# theswitch.net
KiCad netlist of a schematic drawn in Altium Designer
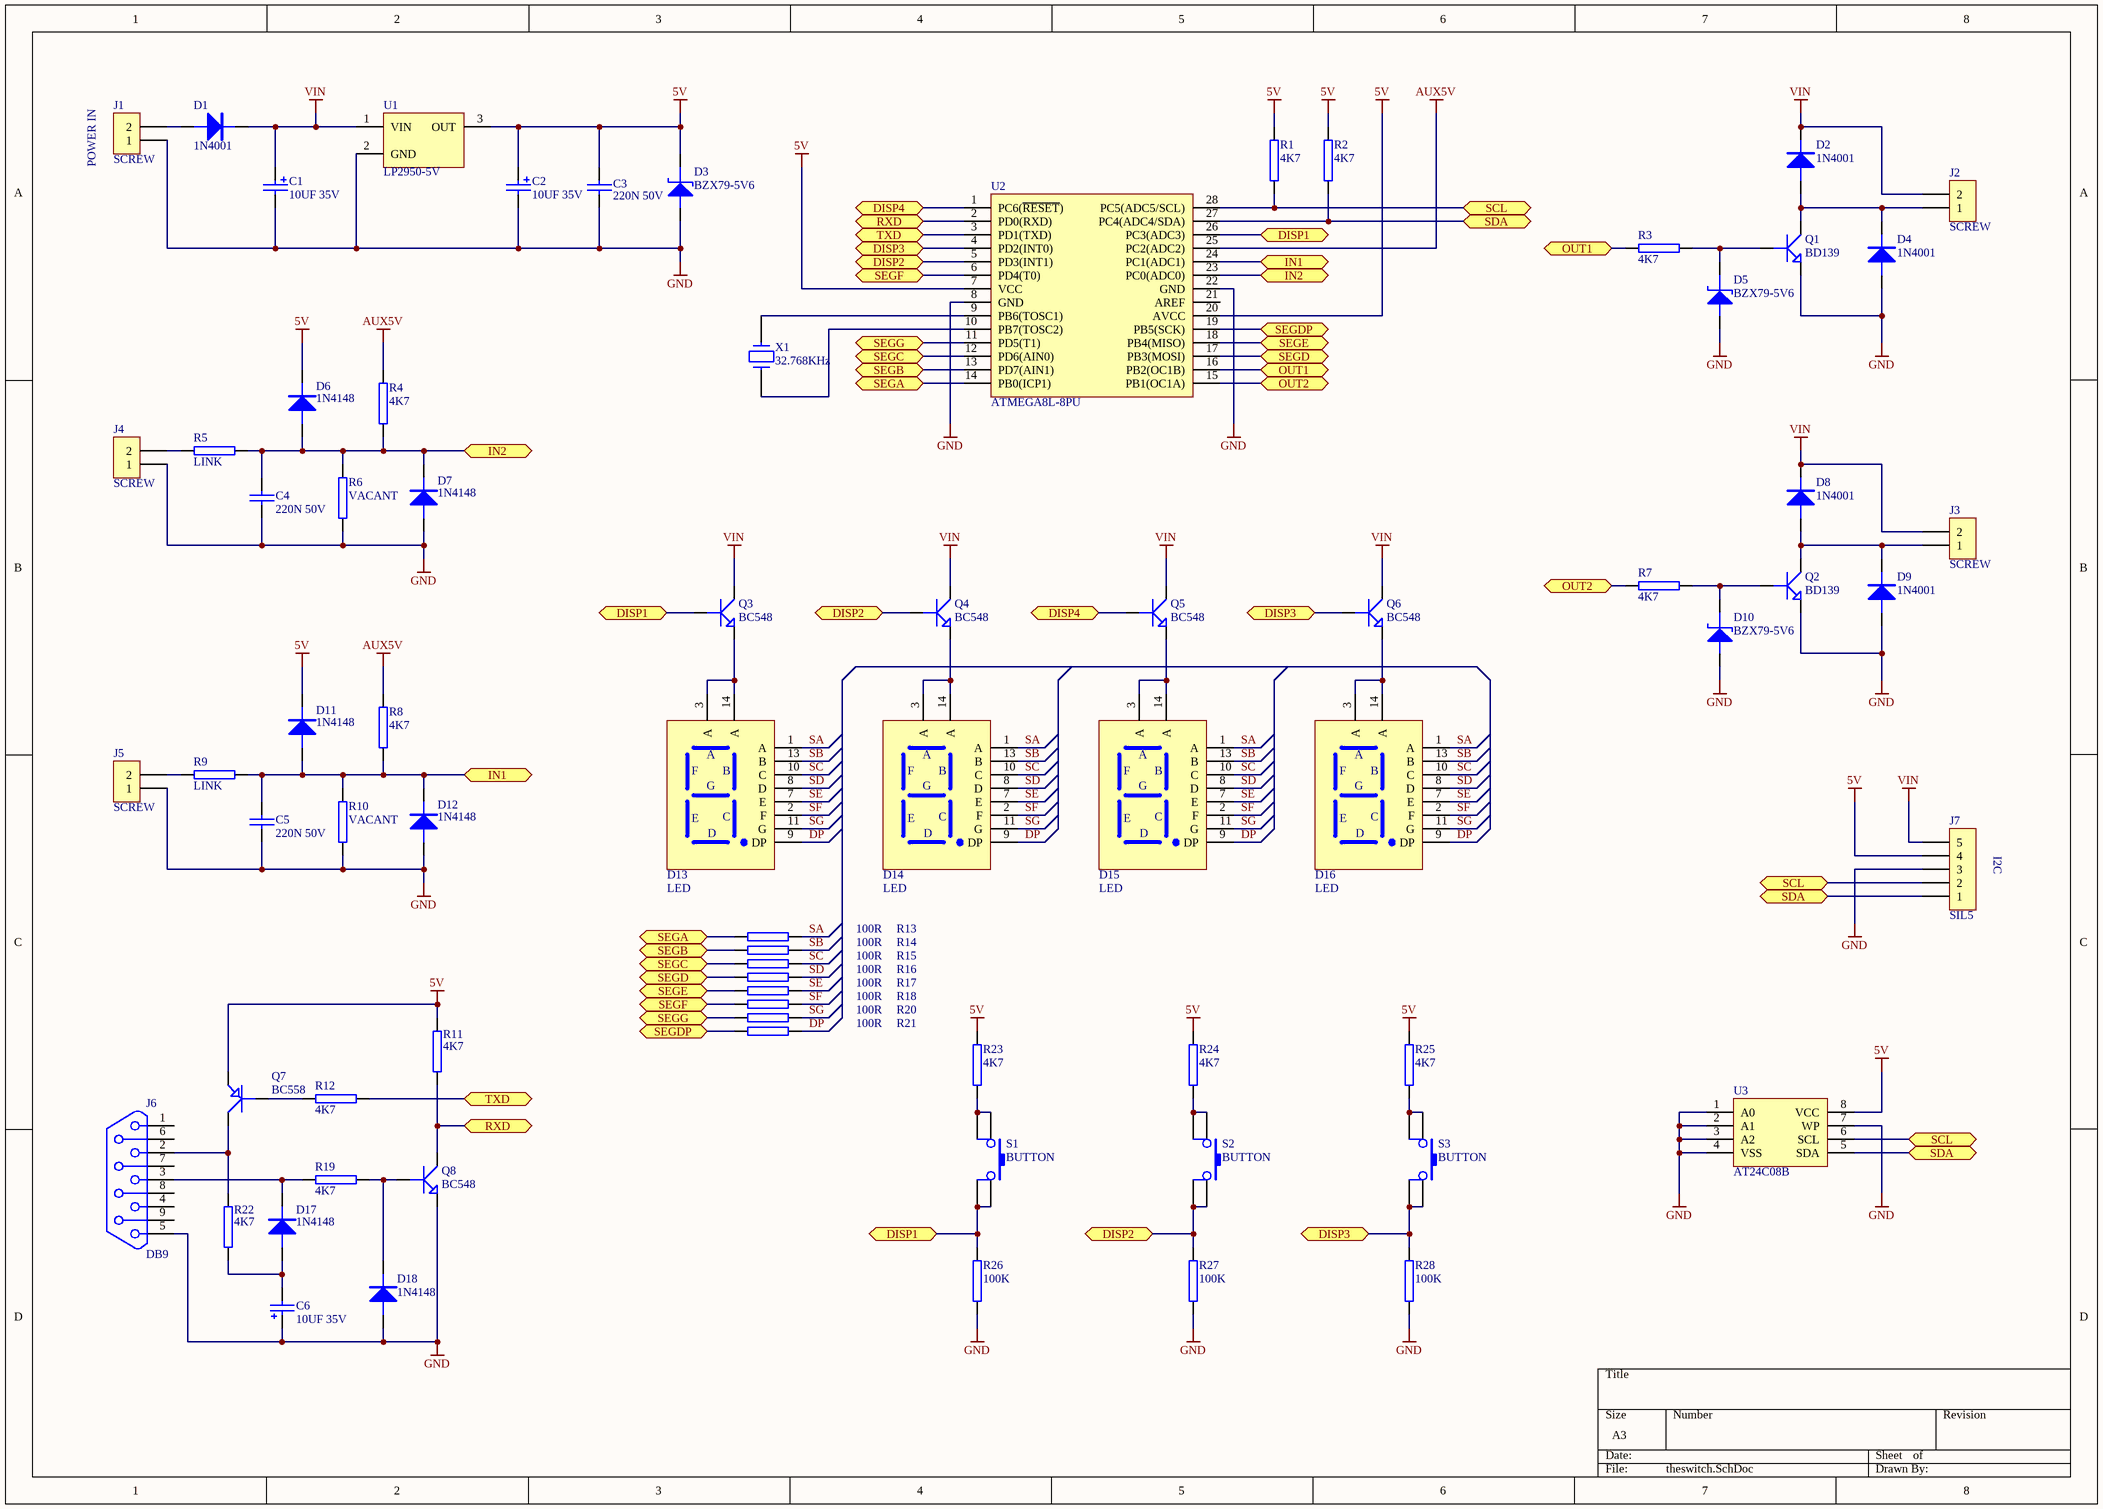
[diagram p0: theswitch.SchDoc]

(export (version "E")
  (design (tool "Eeschema 10.0.6"))
  (components
    (comp (ref "C1")
      (value "10UF 35V")
      (footprint "RADIAL01P")
      (description "CAPACITOR ELECTROLYTIC")
      (libsource (lib "display") (part "CAPPOL"))
    )
    (comp (ref "C2")
      (value "10UF 35V")
      (footprint "RADIAL01P")
      (description "CAPACITOR ELECTROLYTIC")
      (libsource (lib "display") (part "CAPPOL"))
    )
    (comp (ref "C3")
      (value "220N 50V")
      (footprint "RAD02")
      (description "CAPACITOR")
      (libsource (lib "*") (part "CAPACITOR"))
    )
    (comp (ref "C4")
      (value "220N 50V")
      (footprint "RAD02")
      (description "CAPACITOR")
      (libsource (lib "*") (part "CAPACITOR"))
    )
    (comp (ref "C5")
      (value "220N 50V")
      (footprint "RAD02")
      (description "CAPACITOR")
      (libsource (lib "*") (part "CAPACITOR"))
    )
    (comp (ref "C6")
      (value "10UF 35V")
      (footprint "RADIAL01P")
      (description "CAPACITOR ELECTROLYTIC")
      (libsource (lib "display") (part "CAPPOL"))
    )
    (comp (ref "D1") (value "1N4001") (footprint "DO35S") (libsource (lib "*") (part "1N4001")))
    (comp (ref "D2") (value "1N4001") (footprint "DO35S") (libsource (lib "*") (part "1N4001")))
    (comp (ref "D3")
      (value "BZX79-5V6")
      (footprint "DO35S")
      (description "ZENER DIODE")
      (libsource (lib "schlib") (part "BZX79"))
    )
    (comp (ref "D4") (value "1N4001") (footprint "DO35S") (libsource (lib "*") (part "1N4001")))
    (comp (ref "D5")
      (value "BZX79-5V6")
      (footprint "DO35S")
      (description "ZENER DIODE")
      (libsource (lib "schlib") (part "BZX79"))
    )
    (comp (ref "D6") (value "1N4148") (footprint "DO35S") (libsource (lib "1N4148") (part "1N4148")))
    (comp (ref "D7") (value "1N4148") (footprint "DO35S") (libsource (lib "1N4148") (part "1N4148")))
    (comp (ref "D8") (value "1N4001") (footprint "DO35S") (libsource (lib "*") (part "1N4001")))
    (comp (ref "D9") (value "1N4001") (footprint "DO35S") (libsource (lib "*") (part "1N4001")))
    (comp (ref "D10")
      (value "BZX79-5V6")
      (footprint "DO35S")
      (description "ZENER DIODE")
      (libsource (lib "schlib") (part "BZX79"))
    )
    (comp (ref "D11") (value "1N4148") (footprint "DO35S") (libsource (lib "1N4148") (part "1N4148")))
    (comp (ref "D12") (value "1N4148") (footprint "DO35S") (libsource (lib "1N4148") (part "1N4148")))
    (comp (ref "D13")
      (value "LED")
      (footprint "TOS4102")
      (description "LED DISPLAY 7 SEGMENT")
      (libsource (lib "switch") (part "DISP7SEG"))
    )
    (comp (ref "D14")
      (value "LED")
      (footprint "TOS4102")
      (description "LED DISPLAY 7 SEGMENT")
      (libsource (lib "switch") (part "DISP7SEG"))
    )
    (comp (ref "D15")
      (value "LED")
      (footprint "TOS4102")
      (description "LED DISPLAY 7 SEGMENT")
      (libsource (lib "switch") (part "DISP7SEG"))
    )
    (comp (ref "D16")
      (value "LED")
      (footprint "TOS4102")
      (description "LED DISPLAY 7 SEGMENT")
      (libsource (lib "switch") (part "DISP7SEG"))
    )
    (comp (ref "D17") (value "1N4148") (footprint "DO35S") (libsource (lib "1N4148") (part "1N4148")))
    (comp (ref "D18") (value "1N4148") (footprint "DO35S") (libsource (lib "1N4148") (part "1N4148")))
    (comp (ref "J1")
      (value "SCREW")
      (footprint "MKD500S2")
      (description "CONNECTOR")
      (libsource (lib "*") (part "CON2"))
    )
    (comp (ref "J2")
      (value "SCREW")
      (footprint "MKD500S2")
      (description "CONNECTOR")
      (libsource (lib "") (part "CON2_1"))
    )
    (comp (ref "J3")
      (value "SCREW")
      (footprint "MKD500S2")
      (description "CONNECTOR")
      (libsource (lib "") (part "CON2_1"))
    )
    (comp (ref "J4")
      (value "SCREW")
      (footprint "MKD500S2")
      (description "CONNECTOR")
      (libsource (lib "*") (part "CON2"))
    )
    (comp (ref "J5")
      (value "SCREW")
      (footprint "MKD500S2")
      (description "CONNECTOR")
      (libsource (lib "*") (part "CON2"))
    )
    (comp (ref "J6")
      (value "DB9")
      (footprint "DB9S")
      (description "CONNECTOR")
      (libsource (lib "*") (part "DB9"))
    )
    (comp (ref "J7")
      (value "SIL5")
      (footprint "SIL5")
      (description "CONNECTOR")
      (libsource (lib "switch") (part "CON5"))
    )
    (comp (ref "Q1") (value "BD139") (footprint "TO220V") (libsource (lib "theswitch") (part "BD139")))
    (comp (ref "Q2") (value "BD139") (footprint "TO220V") (libsource (lib "theswitch") (part "BD139")))
    (comp (ref "Q3") (value "BC548") (footprint "TO92") (libsource (lib "switch") (part "BC548")))
    (comp (ref "Q4") (value "BC548") (footprint "TO92") (libsource (lib "switch") (part "BC548")))
    (comp (ref "Q5") (value "BC548") (footprint "TO92") (libsource (lib "switch") (part "BC548")))
    (comp (ref "Q6") (value "BC548") (footprint "TO92") (libsource (lib "switch") (part "BC548")))
    (comp (ref "Q7") (value "BC558") (footprint "TO92") (libsource (lib "switch") (part "BC558")))
    (comp (ref "Q8") (value "BC548") (footprint "TO92") (libsource (lib "switch") (part "BC548")))
    (comp (ref "R1")
      (value "4K7")
      (footprint "AXIAL04")
      (description "RESISTOR")
      (libsource (lib "*") (part "RES"))
    )
    (comp (ref "R2")
      (value "4K7")
      (footprint "AXIAL04")
      (description "RESISTOR")
      (libsource (lib "*") (part "RES"))
    )
    (comp (ref "R3")
      (value "4K7")
      (footprint "AXIAL04")
      (description "RESISTOR")
      (libsource (lib "schlib") (part "RES"))
    )
    (comp (ref "R4")
      (value "4K7")
      (footprint "AXIAL04")
      (description "RESISTOR")
      (libsource (lib "*") (part "RES"))
    )
    (comp (ref "R5")
      (value "LINK")
      (footprint "AXIAL04")
      (description "RESISTOR")
      (libsource (lib "*") (part "RES"))
    )
    (comp (ref "R6")
      (value "VACANT")
      (footprint "AXIAL04")
      (description "RESISTOR")
      (libsource (lib "*") (part "RES"))
    )
    (comp (ref "R7")
      (value "4K7")
      (footprint "AXIAL04")
      (description "RESISTOR")
      (libsource (lib "schlib") (part "RES"))
    )
    (comp (ref "R8")
      (value "4K7")
      (footprint "AXIAL04")
      (description "RESISTOR")
      (libsource (lib "*") (part "RES"))
    )
    (comp (ref "R9")
      (value "LINK")
      (footprint "AXIAL04")
      (description "RESISTOR")
      (libsource (lib "*") (part "RES"))
    )
    (comp (ref "R10")
      (value "VACANT")
      (footprint "AXIAL04")
      (description "RESISTOR")
      (libsource (lib "*") (part "RES"))
    )
    (comp (ref "R11")
      (value "4K7")
      (footprint "AXIAL04")
      (description "RESISTOR")
      (libsource (lib "*") (part "RES"))
    )
    (comp (ref "R12")
      (value "4K7")
      (footprint "AXIAL04")
      (description "RESISTOR")
      (libsource (lib "*") (part "RES"))
    )
    (comp (ref "R13")
      (value "100R")
      (footprint "AXIAL04")
      (description "RESISTOR")
      (libsource (lib "*") (part "RES"))
    )
    (comp (ref "R14")
      (value "100R")
      (footprint "AXIAL04")
      (description "RESISTOR")
      (libsource (lib "*") (part "RES"))
    )
    (comp (ref "R15")
      (value "100R")
      (footprint "AXIAL04")
      (description "RESISTOR")
      (libsource (lib "*") (part "RES"))
    )
    (comp (ref "R16")
      (value "100R")
      (footprint "AXIAL04")
      (description "RESISTOR")
      (libsource (lib "*") (part "RES"))
    )
    (comp (ref "R17")
      (value "100R")
      (footprint "AXIAL04")
      (description "RESISTOR")
      (libsource (lib "*") (part "RES"))
    )
    (comp (ref "R18")
      (value "100R")
      (footprint "AXIAL04")
      (description "RESISTOR")
      (libsource (lib "*") (part "RES"))
    )
    (comp (ref "R19")
      (value "4K7")
      (footprint "AXIAL04")
      (description "RESISTOR")
      (libsource (lib "*") (part "RES"))
    )
    (comp (ref "R20")
      (value "100R")
      (footprint "AXIAL04")
      (description "RESISTOR")
      (libsource (lib "*") (part "RES"))
    )
    (comp (ref "R21")
      (value "100R")
      (footprint "AXIAL04")
      (description "RESISTOR")
      (libsource (lib "*") (part "RES"))
    )
    (comp (ref "R22")
      (value "4K7")
      (footprint "AXIAL04")
      (description "RESISTOR")
      (libsource (lib "*") (part "RES"))
    )
    (comp (ref "R23")
      (value "4K7")
      (footprint "AXIAL04")
      (description "RESISTOR")
      (libsource (lib "*") (part "RES"))
    )
    (comp (ref "R24")
      (value "4K7")
      (footprint "AXIAL04")
      (description "RESISTOR")
      (libsource (lib "*") (part "RES"))
    )
    (comp (ref "R25")
      (value "4K7")
      (footprint "AXIAL04")
      (description "RESISTOR")
      (libsource (lib "*") (part "RES"))
    )
    (comp (ref "R26")
      (value "100K")
      (footprint "AXIAL04")
      (description "RESISTOR")
      (libsource (lib "*") (part "RES"))
    )
    (comp (ref "R27")
      (value "100K")
      (footprint "AXIAL04")
      (description "RESISTOR")
      (libsource (lib "*") (part "RES"))
    )
    (comp (ref "R28")
      (value "100K")
      (footprint "AXIAL04")
      (description "RESISTOR")
      (libsource (lib "*") (part "RES"))
    )
    (comp (ref "S1")
      (value "BUTTON")
      (footprint "SWPB")
      (description "PUSH BUTTON SWITCH")
      (libsource (lib "*") (part "BUTTON"))
    )
    (comp (ref "S2")
      (value "BUTTON")
      (footprint "SWPB")
      (description "PUSH BUTTON SWITCH")
      (libsource (lib "*") (part "BUTTON"))
    )
    (comp (ref "S3")
      (value "BUTTON")
      (footprint "SWPB")
      (description "PUSH BUTTON SWITCH")
      (libsource (lib "*") (part "BUTTON"))
    )
    (comp (ref "U1")
      (value "LP2950-5V")
      (footprint "TO92")
      (description "LP2950")
      (libsource (lib "switchkit") (part "LP2950"))
    )
    (comp (ref "U2")
      (value "ATMEGA8L-8PU")
      (footprint "DIP28N")
      (description "MICROCONTROLLER")
      (libsource (lib "switchkit") (part "ATMEGA8L-8PU"))
    )
    (comp (ref "U3")
      (value "AT24C08B")
      (footprint "DIP8")
      (description "I2C 8KBIT EEPROM")
      (libsource (lib "switch") (part "AT24C08B"))
    )
    (comp (ref "X1")
      (value "32.768KHz")
      (footprint "RADIAL01")
      (description "CRYSTAL")
      (libsource (lib "*") (part "XTAL"))
    )
  )
  (nets
    (net (code "1") (name "/DISP1") (class "Default")
      (node (ref "Q3") (pin "2") (pinfunction "B_2") (pintype "passive"))
      (node (ref "R26") (pin "2") (pinfunction "2_2") (pintype "passive"))
      (node (ref "S1") (pin "2") (pinfunction "2_2") (pintype "passive"))
      (node (ref "S1") (pin "4") (pinfunction "4_4") (pintype "passive"))
      (node (ref "U2") (pin "26") (pinfunction "PC3(ADC3)_26") (pintype "passive"))
    )
    (net (code "2") (name "/DISP2") (class "Default")
      (node (ref "Q4") (pin "2") (pinfunction "B_2") (pintype "passive"))
      (node (ref "R27") (pin "2") (pinfunction "2_2") (pintype "passive"))
      (node (ref "S2") (pin "2") (pinfunction "2_2") (pintype "passive"))
      (node (ref "S2") (pin "4") (pinfunction "4_4") (pintype "passive"))
      (node (ref "U2") (pin "5") (pinfunction "PD3(INT1)_5") (pintype "power_in"))
    )
    (net (code "3") (name "/DISP3") (class "Default")
      (node (ref "Q6") (pin "2") (pinfunction "B_2") (pintype "passive"))
      (node (ref "R28") (pin "2") (pinfunction "2_2") (pintype "passive"))
      (node (ref "S3") (pin "2") (pinfunction "2_2") (pintype "passive"))
      (node (ref "S3") (pin "4") (pinfunction "4_4") (pintype "passive"))
      (node (ref "U2") (pin "4") (pinfunction "PD2(INT0)_4") (pintype "passive"))
    )
    (net (code "4") (name "/DISP4") (class "Default")
      (node (ref "Q5") (pin "2") (pinfunction "B_2") (pintype "passive"))
      (node (ref "U2") (pin "1") (pinfunction "PC6(~{RESET})_1") (pintype "passive"))
    )
    (net (code "5") (name "/DP") (class "Default")
      (node (ref "D13") (pin "9") (pinfunction "DP_9") (pintype "passive"))
      (node (ref "D14") (pin "9") (pinfunction "DP_9") (pintype "passive"))
      (node (ref "D15") (pin "9") (pinfunction "DP_9") (pintype "passive"))
      (node (ref "D16") (pin "9") (pinfunction "DP_9") (pintype "passive"))
      (node (ref "R21") (pin "2") (pinfunction "2_2") (pintype "passive"))
    )
    (net (code "6") (name "/IN1") (class "Default")
      (node (ref "C5") (pin "1") (pinfunction "1_1") (pintype "passive"))
      (node (ref "D11") (pin "1") (pinfunction "A_1") (pintype "passive"))
      (node (ref "D12") (pin "2") (pinfunction "K_2") (pintype "passive"))
      (node (ref "R10") (pin "1") (pinfunction "1_1") (pintype "passive"))
      (node (ref "R8") (pin "2") (pinfunction "2_2") (pintype "passive"))
      (node (ref "R9") (pin "2") (pinfunction "2_2") (pintype "passive"))
      (node (ref "U2") (pin "24") (pinfunction "PC1(ADC1)_24") (pintype "passive"))
    )
    (net (code "7") (name "/IN2") (class "Default")
      (node (ref "C4") (pin "1") (pinfunction "1_1") (pintype "passive"))
      (node (ref "D6") (pin "1") (pinfunction "A_1") (pintype "passive"))
      (node (ref "D7") (pin "2") (pinfunction "K_2") (pintype "passive"))
      (node (ref "R4") (pin "2") (pinfunction "2_2") (pintype "passive"))
      (node (ref "R5") (pin "2") (pinfunction "2_2") (pintype "passive"))
      (node (ref "R6") (pin "1") (pinfunction "1_1") (pintype "passive"))
      (node (ref "U2") (pin "23") (pinfunction "PC0(ADC0)_23") (pintype "passive"))
    )
    (net (code "8") (name "/OUT1") (class "Default")
      (node (ref "R3") (pin "2") (pinfunction "2_2") (pintype "passive"))
      (node (ref "U2") (pin "16") (pinfunction "PB2(OC1B)_16") (pintype "passive"))
    )
    (net (code "9") (name "/OUT2") (class "Default")
      (node (ref "R7") (pin "2") (pinfunction "2_2") (pintype "passive"))
      (node (ref "U2") (pin "15") (pinfunction "PB1(OC1A)_15") (pintype "passive"))
    )
    (net (code "10") (name "/RXD") (class "Default")
      (node (ref "Q8") (pin "3") (pinfunction "C_3") (pintype "passive"))
      (node (ref "R11") (pin "1") (pinfunction "1_1") (pintype "passive"))
      (node (ref "U2") (pin "2") (pinfunction "PD0(RXD)_2") (pintype "passive"))
    )
    (net (code "11") (name "/SA") (class "Default")
      (node (ref "D13") (pin "1") (pinfunction "A_1") (pintype "passive"))
      (node (ref "D14") (pin "1") (pinfunction "A_1") (pintype "passive"))
      (node (ref "D15") (pin "1") (pinfunction "A_1") (pintype "passive"))
      (node (ref "D16") (pin "1") (pinfunction "A_1") (pintype "passive"))
      (node (ref "R13") (pin "2") (pinfunction "2_2") (pintype "passive"))
    )
    (net (code "12") (name "/SB") (class "Default")
      (node (ref "D13") (pin "13") (pinfunction "B_13") (pintype "passive"))
      (node (ref "D14") (pin "13") (pinfunction "B_13") (pintype "passive"))
      (node (ref "D15") (pin "13") (pinfunction "B_13") (pintype "passive"))
      (node (ref "D16") (pin "13") (pinfunction "B_13") (pintype "passive"))
      (node (ref "R14") (pin "2") (pinfunction "2_2") (pintype "passive"))
    )
    (net (code "13") (name "/SC") (class "Default")
      (node (ref "D13") (pin "10") (pinfunction "C_10") (pintype "passive"))
      (node (ref "D14") (pin "10") (pinfunction "C_10") (pintype "passive"))
      (node (ref "D15") (pin "10") (pinfunction "C_10") (pintype "passive"))
      (node (ref "D16") (pin "10") (pinfunction "C_10") (pintype "passive"))
      (node (ref "R15") (pin "2") (pinfunction "2_2") (pintype "passive"))
    )
    (net (code "14") (name "/SCL") (class "Default")
      (node (ref "J7") (pin "2") (pinfunction "2_2") (pintype "passive"))
      (node (ref "R1") (pin "1") (pinfunction "1_1") (pintype "passive"))
      (node (ref "U2") (pin "28") (pinfunction "PC5(ADC5/SCL)_28") (pintype "passive"))
      (node (ref "U3") (pin "6") (pinfunction "SCL_6") (pintype "passive"))
    )
    (net (code "15") (name "/SD") (class "Default")
      (node (ref "D13") (pin "8") (pinfunction "D_8") (pintype "passive"))
      (node (ref "D14") (pin "8") (pinfunction "D_8") (pintype "passive"))
      (node (ref "D15") (pin "8") (pinfunction "D_8") (pintype "passive"))
      (node (ref "D16") (pin "8") (pinfunction "D_8") (pintype "passive"))
      (node (ref "R16") (pin "2") (pinfunction "2_2") (pintype "passive"))
    )
    (net (code "16") (name "/SDA") (class "Default")
      (node (ref "J7") (pin "1") (pinfunction "1_1") (pintype "passive"))
      (node (ref "R2") (pin "1") (pinfunction "1_1") (pintype "passive"))
      (node (ref "U2") (pin "27") (pinfunction "PC4(ADC4/SDA)_27") (pintype "passive"))
      (node (ref "U3") (pin "5") (pinfunction "SDA_5") (pintype "passive"))
    )
    (net (code "17") (name "/SE") (class "Default")
      (node (ref "D13") (pin "7") (pinfunction "E_7") (pintype "passive"))
      (node (ref "D14") (pin "7") (pinfunction "E_7") (pintype "passive"))
      (node (ref "D15") (pin "7") (pinfunction "E_7") (pintype "passive"))
      (node (ref "D16") (pin "7") (pinfunction "E_7") (pintype "passive"))
      (node (ref "R17") (pin "2") (pinfunction "2_2") (pintype "passive"))
    )
    (net (code "18") (name "/SEGA") (class "Default")
      (node (ref "R13") (pin "1") (pinfunction "1_1") (pintype "passive"))
      (node (ref "U2") (pin "14") (pinfunction "PB0(ICP1)_14") (pintype "passive"))
    )
    (net (code "19") (name "/SEGB") (class "Default")
      (node (ref "R14") (pin "1") (pinfunction "1_1") (pintype "passive"))
      (node (ref "U2") (pin "13") (pinfunction "PD7(AIN1)_13") (pintype "passive"))
    )
    (net (code "20") (name "/SEGC") (class "Default")
      (node (ref "R15") (pin "1") (pinfunction "1_1") (pintype "passive"))
      (node (ref "U2") (pin "12") (pinfunction "PD6(AIN0)_12") (pintype "passive"))
    )
    (net (code "21") (name "/SEGD") (class "Default")
      (node (ref "R16") (pin "1") (pinfunction "1_1") (pintype "passive"))
      (node (ref "U2") (pin "17") (pinfunction "PB3(MOSI)_17") (pintype "passive"))
    )
    (net (code "22") (name "/SEGDP") (class "Default")
      (node (ref "R21") (pin "1") (pinfunction "1_1") (pintype "passive"))
      (node (ref "U2") (pin "19") (pinfunction "PB5(SCK)_19") (pintype "passive"))
    )
    (net (code "23") (name "/SEGE") (class "Default")
      (node (ref "R17") (pin "1") (pinfunction "1_1") (pintype "passive"))
      (node (ref "U2") (pin "18") (pinfunction "PB4(MISO)_18") (pintype "passive"))
    )
    (net (code "24") (name "/SEGF") (class "Default")
      (node (ref "R18") (pin "1") (pinfunction "1_1") (pintype "passive"))
      (node (ref "U2") (pin "6") (pinfunction "PD4(T0)_6") (pintype "power_in"))
    )
    (net (code "25") (name "/SEGG") (class "Default")
      (node (ref "R20") (pin "1") (pinfunction "1_1") (pintype "passive"))
      (node (ref "U2") (pin "11") (pinfunction "PD5(T1)_11") (pintype "passive"))
    )
    (net (code "26") (name "/SF") (class "Default")
      (node (ref "D13") (pin "2") (pinfunction "F_2") (pintype "passive"))
      (node (ref "D14") (pin "2") (pinfunction "F_2") (pintype "passive"))
      (node (ref "D15") (pin "2") (pinfunction "F_2") (pintype "passive"))
      (node (ref "D16") (pin "2") (pinfunction "F_2") (pintype "passive"))
      (node (ref "R18") (pin "2") (pinfunction "2_2") (pintype "passive"))
    )
    (net (code "27") (name "/SG") (class "Default")
      (node (ref "D13") (pin "11") (pinfunction "G_11") (pintype "passive"))
      (node (ref "D14") (pin "11") (pinfunction "G_11") (pintype "passive"))
      (node (ref "D15") (pin "11") (pinfunction "G_11") (pintype "passive"))
      (node (ref "D16") (pin "11") (pinfunction "G_11") (pintype "passive"))
      (node (ref "R20") (pin "2") (pinfunction "2_2") (pintype "passive"))
    )
    (net (code "28") (name "/TXD") (class "Default")
      (node (ref "R12") (pin "1") (pinfunction "1_1") (pintype "passive"))
      (node (ref "U2") (pin "3") (pinfunction "PD1(TXD)_3") (pintype "passive"))
    )
    (net (code "29") (name "5V") (class "Default")
      (node (ref "C2") (pin "1") (pinfunction "1_1") (pintype "passive"))
      (node (ref "C3") (pin "1") (pinfunction "1_1") (pintype "passive"))
      (node (ref "D11") (pin "2") (pinfunction "K_2") (pintype "passive"))
      (node (ref "D3") (pin "2") (pinfunction "K_2") (pintype "passive"))
      (node (ref "D6") (pin "2") (pinfunction "K_2") (pintype "passive"))
      (node (ref "J7") (pin "4") (pinfunction "4_4") (pintype "passive"))
      (node (ref "Q7") (pin "1") (pinfunction "E_1") (pintype "passive"))
      (node (ref "R1") (pin "2") (pinfunction "2_2") (pintype "passive"))
      (node (ref "R11") (pin "2") (pinfunction "2_2") (pintype "passive"))
      (node (ref "R2") (pin "2") (pinfunction "2_2") (pintype "passive"))
      (node (ref "R23") (pin "2") (pinfunction "2_2") (pintype "passive"))
      (node (ref "R24") (pin "2") (pinfunction "2_2") (pintype "passive"))
      (node (ref "R25") (pin "2") (pinfunction "2_2") (pintype "passive"))
      (node (ref "U1") (pin "3") (pinfunction "OUT_3") (pintype "passive"))
      (node (ref "U2") (pin "20") (pinfunction "AVCC_20") (pintype "passive"))
      (node (ref "U2") (pin "7") (pinfunction "VCC_7") (pintype "passive"))
      (node (ref "U3") (pin "8") (pinfunction "VCC_8") (pintype "passive"))
    )
    (net (code "30") (name "AUX5V") (class "Default")
      (node (ref "R4") (pin "1") (pinfunction "1_1") (pintype "passive"))
      (node (ref "R8") (pin "1") (pinfunction "1_1") (pintype "passive"))
      (node (ref "U2") (pin "25") (pinfunction "PC2(ADC2)_25") (pintype "passive"))
    )
    (net (code "31") (name "GND") (class "Default")
      (node (ref "C1") (pin "2") (pinfunction "2_2") (pintype "passive"))
      (node (ref "C2") (pin "2") (pinfunction "2_2") (pintype "passive"))
      (node (ref "C3") (pin "2") (pinfunction "2_2") (pintype "passive"))
      (node (ref "C4") (pin "2") (pinfunction "2_2") (pintype "passive"))
      (node (ref "C5") (pin "2") (pinfunction "2_2") (pintype "passive"))
      (node (ref "C6") (pin "1") (pinfunction "1_1") (pintype "passive"))
      (node (ref "D10") (pin "1") (pinfunction "A_1") (pintype "passive"))
      (node (ref "D12") (pin "1") (pinfunction "A_1") (pintype "passive"))
      (node (ref "D18") (pin "1") (pinfunction "A_1") (pintype "passive"))
      (node (ref "D3") (pin "1") (pinfunction "A_1") (pintype "passive"))
      (node (ref "D4") (pin "1") (pinfunction "A_1") (pintype "passive"))
      (node (ref "D5") (pin "1") (pinfunction "A_1") (pintype "passive"))
      (node (ref "D7") (pin "1") (pinfunction "A_1") (pintype "passive"))
      (node (ref "D9") (pin "1") (pinfunction "A_1") (pintype "passive"))
      (node (ref "J1") (pin "1") (pinfunction "1_1") (pintype "passive"))
      (node (ref "J4") (pin "1") (pinfunction "1_1") (pintype "passive"))
      (node (ref "J5") (pin "1") (pinfunction "1_1") (pintype "passive"))
      (node (ref "J6") (pin "5") (pinfunction "5_5") (pintype "passive"))
      (node (ref "J7") (pin "3") (pinfunction "3_3") (pintype "passive"))
      (node (ref "Q1") (pin "1") (pinfunction "E_1") (pintype "passive"))
      (node (ref "Q2") (pin "1") (pinfunction "E_1") (pintype "passive"))
      (node (ref "Q8") (pin "1") (pinfunction "E_1") (pintype "passive"))
      (node (ref "R10") (pin "2") (pinfunction "2_2") (pintype "passive"))
      (node (ref "R26") (pin "1") (pinfunction "1_1") (pintype "passive"))
      (node (ref "R27") (pin "1") (pinfunction "1_1") (pintype "passive"))
      (node (ref "R28") (pin "1") (pinfunction "1_1") (pintype "passive"))
      (node (ref "R6") (pin "2") (pinfunction "2_2") (pintype "passive"))
      (node (ref "U1") (pin "2") (pinfunction "GND_2") (pintype "power_in"))
      (node (ref "U2") (pin "22") (pinfunction "GND_22") (pintype "passive"))
      (node (ref "U2") (pin "8") (pinfunction "GND_8") (pintype "passive"))
      (node (ref "U3") (pin "1") (pinfunction "A0_1") (pintype "passive"))
      (node (ref "U3") (pin "2") (pinfunction "A1_2") (pintype "passive"))
      (node (ref "U3") (pin "3") (pinfunction "A2_3") (pintype "passive"))
      (node (ref "U3") (pin "4") (pinfunction "VSS_4") (pintype "passive"))
      (node (ref "U3") (pin "7") (pinfunction "WP_7") (pintype "passive"))
    )
    (net (code "32") (name "Net-(D1-A)") (class "Default")
      (node (ref "D1") (pin "1") (pinfunction "A_1") (pintype "passive"))
      (node (ref "J1") (pin "2") (pinfunction "2_2") (pintype "passive"))
    )
    (net (code "33") (name "Net-(D2-A)") (class "Default")
      (node (ref "D2") (pin "1") (pinfunction "A_1") (pintype "passive"))
      (node (ref "D4") (pin "2") (pinfunction "K_2") (pintype "passive"))
      (node (ref "J2") (pin "1") (pinfunction "1_1") (pintype "passive"))
      (node (ref "Q1") (pin "2") (pinfunction "C_2") (pintype "passive"))
    )
    (net (code "34") (name "Net-(D5-K)") (class "Default")
      (node (ref "D5") (pin "2") (pinfunction "K_2") (pintype "passive"))
      (node (ref "Q1") (pin "3") (pinfunction "B_3") (pintype "passive"))
      (node (ref "R3") (pin "1") (pinfunction "1_1") (pintype "passive"))
    )
    (net (code "35") (name "Net-(D8-A)") (class "Default")
      (node (ref "D8") (pin "1") (pinfunction "A_1") (pintype "passive"))
      (node (ref "D9") (pin "2") (pinfunction "K_2") (pintype "passive"))
      (node (ref "J3") (pin "1") (pinfunction "1_1") (pintype "passive"))
      (node (ref "Q2") (pin "2") (pinfunction "C_2") (pintype "passive"))
    )
    (net (code "36") (name "Net-(D10-K)") (class "Default")
      (node (ref "D10") (pin "2") (pinfunction "K_2") (pintype "passive"))
      (node (ref "Q2") (pin "3") (pinfunction "B_3") (pintype "passive"))
      (node (ref "R7") (pin "1") (pinfunction "1_1") (pintype "passive"))
    )
    (net (code "37") (name "Net-(D17-A)") (class "Default")
      (node (ref "C6") (pin "2") (pinfunction "2_2") (pintype "passive"))
      (node (ref "D17") (pin "1") (pinfunction "A_1") (pintype "passive"))
      (node (ref "R22") (pin "1") (pinfunction "1_1") (pintype "passive"))
    )
    (net (code "38") (name "Net-(D17-K)") (class "Default")
      (node (ref "D17") (pin "2") (pinfunction "K_2") (pintype "passive"))
      (node (ref "J6") (pin "3") (pinfunction "3_3") (pintype "passive"))
      (node (ref "R19") (pin "2") (pinfunction "2_2") (pintype "passive"))
    )
    (net (code "39") (name "Net-(D18-K)") (class "Default")
      (node (ref "D18") (pin "2") (pinfunction "K_2") (pintype "passive"))
      (node (ref "Q8") (pin "2") (pinfunction "B_2") (pintype "passive"))
      (node (ref "R19") (pin "1") (pinfunction "1_1") (pintype "passive"))
    )
    (net (code "40") (name "Net-(J4-Pad2)") (class "Default")
      (node (ref "J4") (pin "2") (pinfunction "2_2") (pintype "passive"))
      (node (ref "R5") (pin "1") (pinfunction "1_1") (pintype "passive"))
    )
    (net (code "41") (name "Net-(J5-Pad2)") (class "Default")
      (node (ref "J5") (pin "2") (pinfunction "2_2") (pintype "passive"))
      (node (ref "R9") (pin "1") (pinfunction "1_1") (pintype "passive"))
    )
    (net (code "42") (name "Net-(Q3-E)") (class "Default")
      (node (ref "D13") (pin "14") (pinfunction "A_14") (pintype "passive"))
      (node (ref "D13") (pin "3") (pinfunction "A_3") (pintype "passive"))
      (node (ref "Q3") (pin "1") (pinfunction "E_1") (pintype "passive"))
    )
    (net (code "43") (name "Net-(Q4-E)") (class "Default")
      (node (ref "D14") (pin "14") (pinfunction "A_14") (pintype "passive"))
      (node (ref "D14") (pin "3") (pinfunction "A_3") (pintype "passive"))
      (node (ref "Q4") (pin "1") (pinfunction "E_1") (pintype "passive"))
    )
    (net (code "44") (name "Net-(Q5-E)") (class "Default")
      (node (ref "D15") (pin "14") (pinfunction "A_14") (pintype "passive"))
      (node (ref "D15") (pin "3") (pinfunction "A_3") (pintype "passive"))
      (node (ref "Q5") (pin "1") (pinfunction "E_1") (pintype "passive"))
    )
    (net (code "45") (name "Net-(Q6-E)") (class "Default")
      (node (ref "D16") (pin "14") (pinfunction "A_14") (pintype "passive"))
      (node (ref "D16") (pin "3") (pinfunction "A_3") (pintype "passive"))
      (node (ref "Q6") (pin "1") (pinfunction "E_1") (pintype "passive"))
    )
    (net (code "46") (name "Net-(Q7-B)") (class "Default")
      (node (ref "Q7") (pin "2") (pinfunction "B_2") (pintype "passive"))
      (node (ref "R12") (pin "2") (pinfunction "2_2") (pintype "passive"))
    )
    (net (code "47") (name "Net-(Q7-C)") (class "Default")
      (node (ref "J6") (pin "2") (pinfunction "2_2") (pintype "passive"))
      (node (ref "Q7") (pin "3") (pinfunction "C_3") (pintype "passive"))
      (node (ref "R22") (pin "2") (pinfunction "2_2") (pintype "passive"))
    )
    (net (code "48") (name "Net-(R23-Pad1)") (class "Default")
      (node (ref "R23") (pin "1") (pinfunction "1_1") (pintype "passive"))
      (node (ref "S1") (pin "1") (pinfunction "1_1") (pintype "passive"))
      (node (ref "S1") (pin "3") (pinfunction "3_3") (pintype "passive"))
    )
    (net (code "49") (name "Net-(R24-Pad1)") (class "Default")
      (node (ref "R24") (pin "1") (pinfunction "1_1") (pintype "passive"))
      (node (ref "S2") (pin "1") (pinfunction "1_1") (pintype "passive"))
      (node (ref "S2") (pin "3") (pinfunction "3_3") (pintype "passive"))
    )
    (net (code "50") (name "Net-(R25-Pad1)") (class "Default")
      (node (ref "R25") (pin "1") (pinfunction "1_1") (pintype "passive"))
      (node (ref "S3") (pin "1") (pinfunction "1_1") (pintype "passive"))
      (node (ref "S3") (pin "3") (pinfunction "3_3") (pintype "passive"))
    )
    (net (code "51") (name "Net-(U2-PB6(TOSC1))") (class "Default")
      (node (ref "U2") (pin "9") (pinfunction "PB6(TOSC1)_9") (pintype "passive"))
      (node (ref "X1") (pin "1") (pinfunction "1_1") (pintype "passive"))
    )
    (net (code "52") (name "Net-(U2-PB7(TOSC2))") (class "Default")
      (node (ref "U2") (pin "10") (pinfunction "PB7(TOSC2)_10") (pintype "passive"))
      (node (ref "X1") (pin "2") (pinfunction "2_2") (pintype "passive"))
    )
    (net (code "53") (name "VIN") (class "Default")
      (node (ref "C1") (pin "1") (pinfunction "1_1") (pintype "passive"))
      (node (ref "D1") (pin "2") (pinfunction "K_2") (pintype "passive"))
      (node (ref "D2") (pin "2") (pinfunction "K_2") (pintype "passive"))
      (node (ref "D8") (pin "2") (pinfunction "K_2") (pintype "passive"))
      (node (ref "J2") (pin "2") (pinfunction "2_2") (pintype "passive"))
      (node (ref "J3") (pin "2") (pinfunction "2_2") (pintype "passive"))
      (node (ref "J7") (pin "5") (pinfunction "5_5") (pintype "passive"))
      (node (ref "Q3") (pin "3") (pinfunction "C_3") (pintype "passive"))
      (node (ref "Q4") (pin "3") (pinfunction "C_3") (pintype "passive"))
      (node (ref "Q5") (pin "3") (pinfunction "C_3") (pintype "passive"))
      (node (ref "Q6") (pin "3") (pinfunction "C_3") (pintype "passive"))
      (node (ref "U1") (pin "1") (pinfunction "VIN_1") (pintype "passive"))
    )
    (net (code "54") (name "unconnected-(J6-Pad1)") (class "Default")
      (node (ref "J6") (pin "1") (pinfunction "1_1") (pintype "passive"))
    )
    (net (code "55") (name "unconnected-(J6-Pad4)") (class "Default")
      (node (ref "J6") (pin "4") (pinfunction "4_4") (pintype "passive"))
    )
    (net (code "56") (name "unconnected-(J6-Pad6)") (class "Default")
      (node (ref "J6") (pin "6") (pinfunction "6_6") (pintype "passive"))
    )
    (net (code "57") (name "unconnected-(J6-Pad7)") (class "Default")
      (node (ref "J6") (pin "7") (pinfunction "7_7") (pintype "passive"))
    )
    (net (code "58") (name "unconnected-(J6-Pad8)") (class "Default")
      (node (ref "J6") (pin "8") (pinfunction "8_8") (pintype "passive"))
    )
    (net (code "59") (name "unconnected-(J6-Pad9)") (class "Default")
      (node (ref "J6") (pin "9") (pinfunction "9_9") (pintype "passive"))
    )
    (net (code "60") (name "unconnected-(U2-AREF-Pad21)") (class "Default")
      (node (ref "U2") (pin "21") (pinfunction "AREF_21") (pintype "passive"))
    )
  )
)
